# M2_NVME.net
KiCad netlist of a schematic drawn in Altium Designer
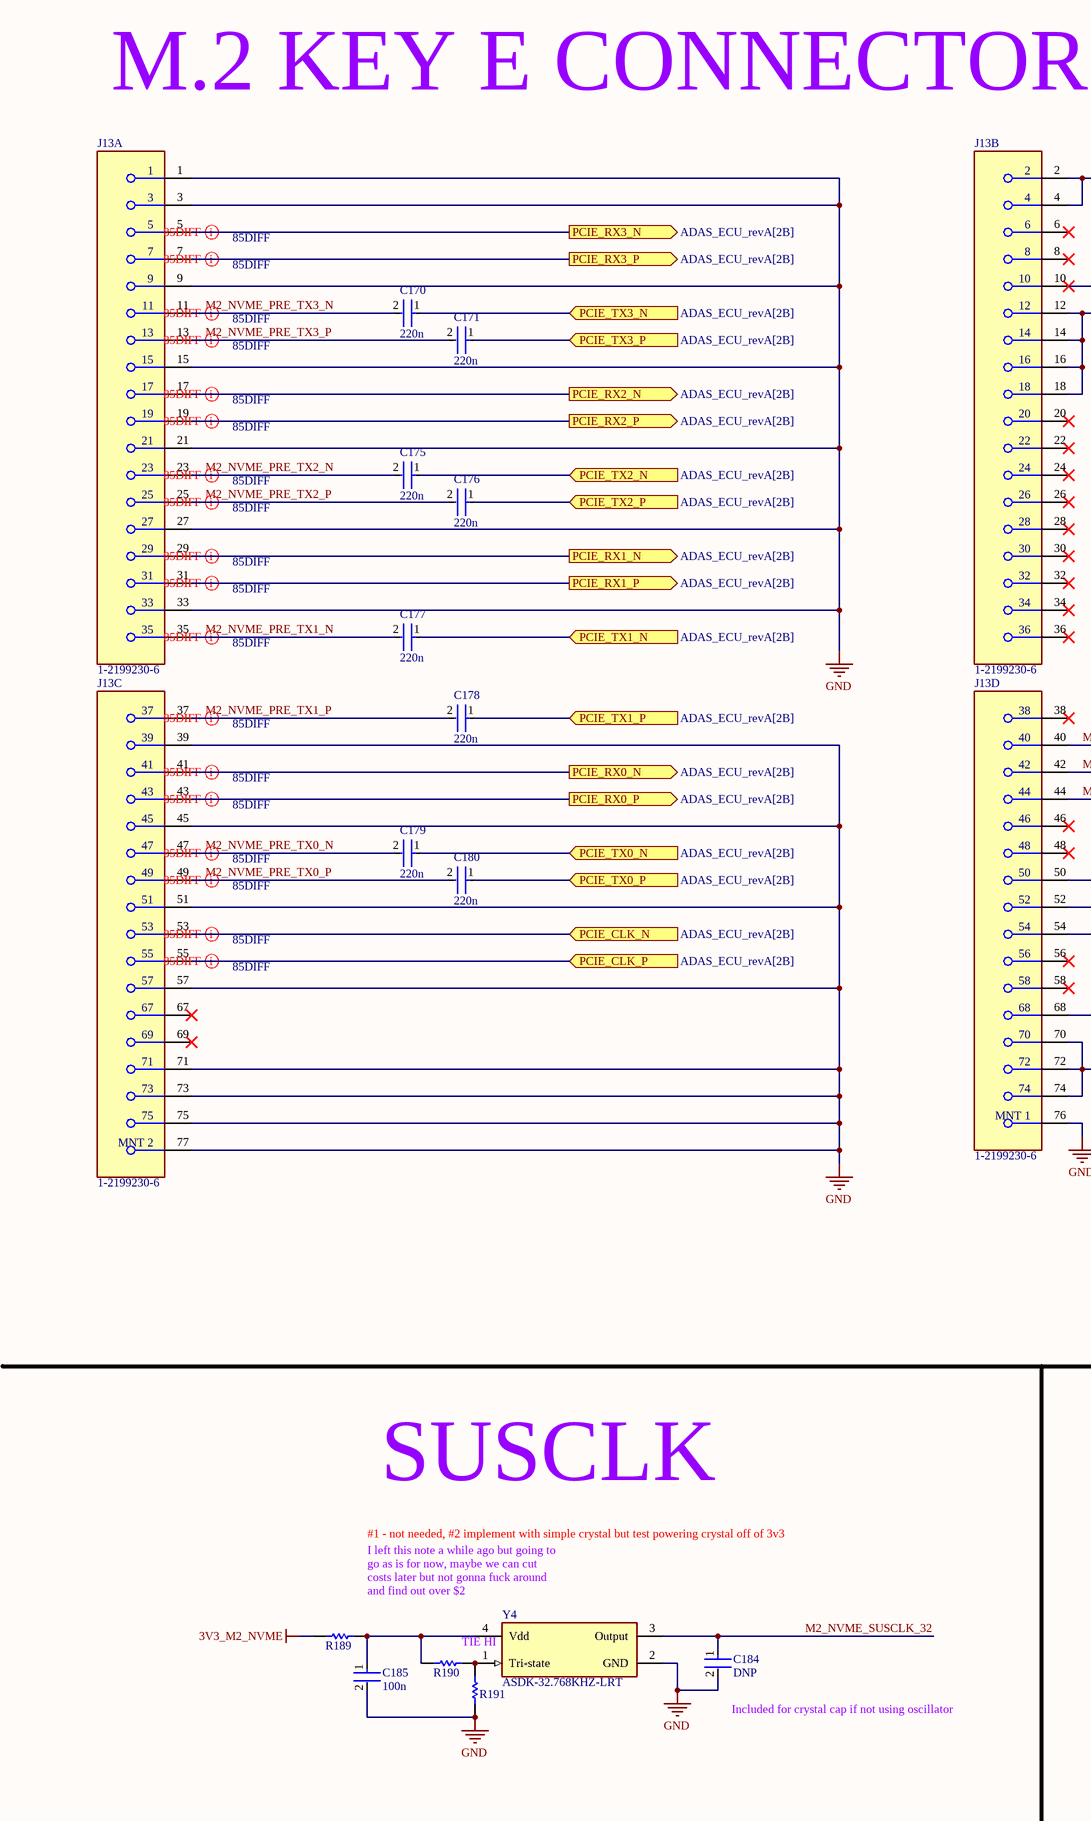
[diagram p0: M2_NVME.SchDoc, left]
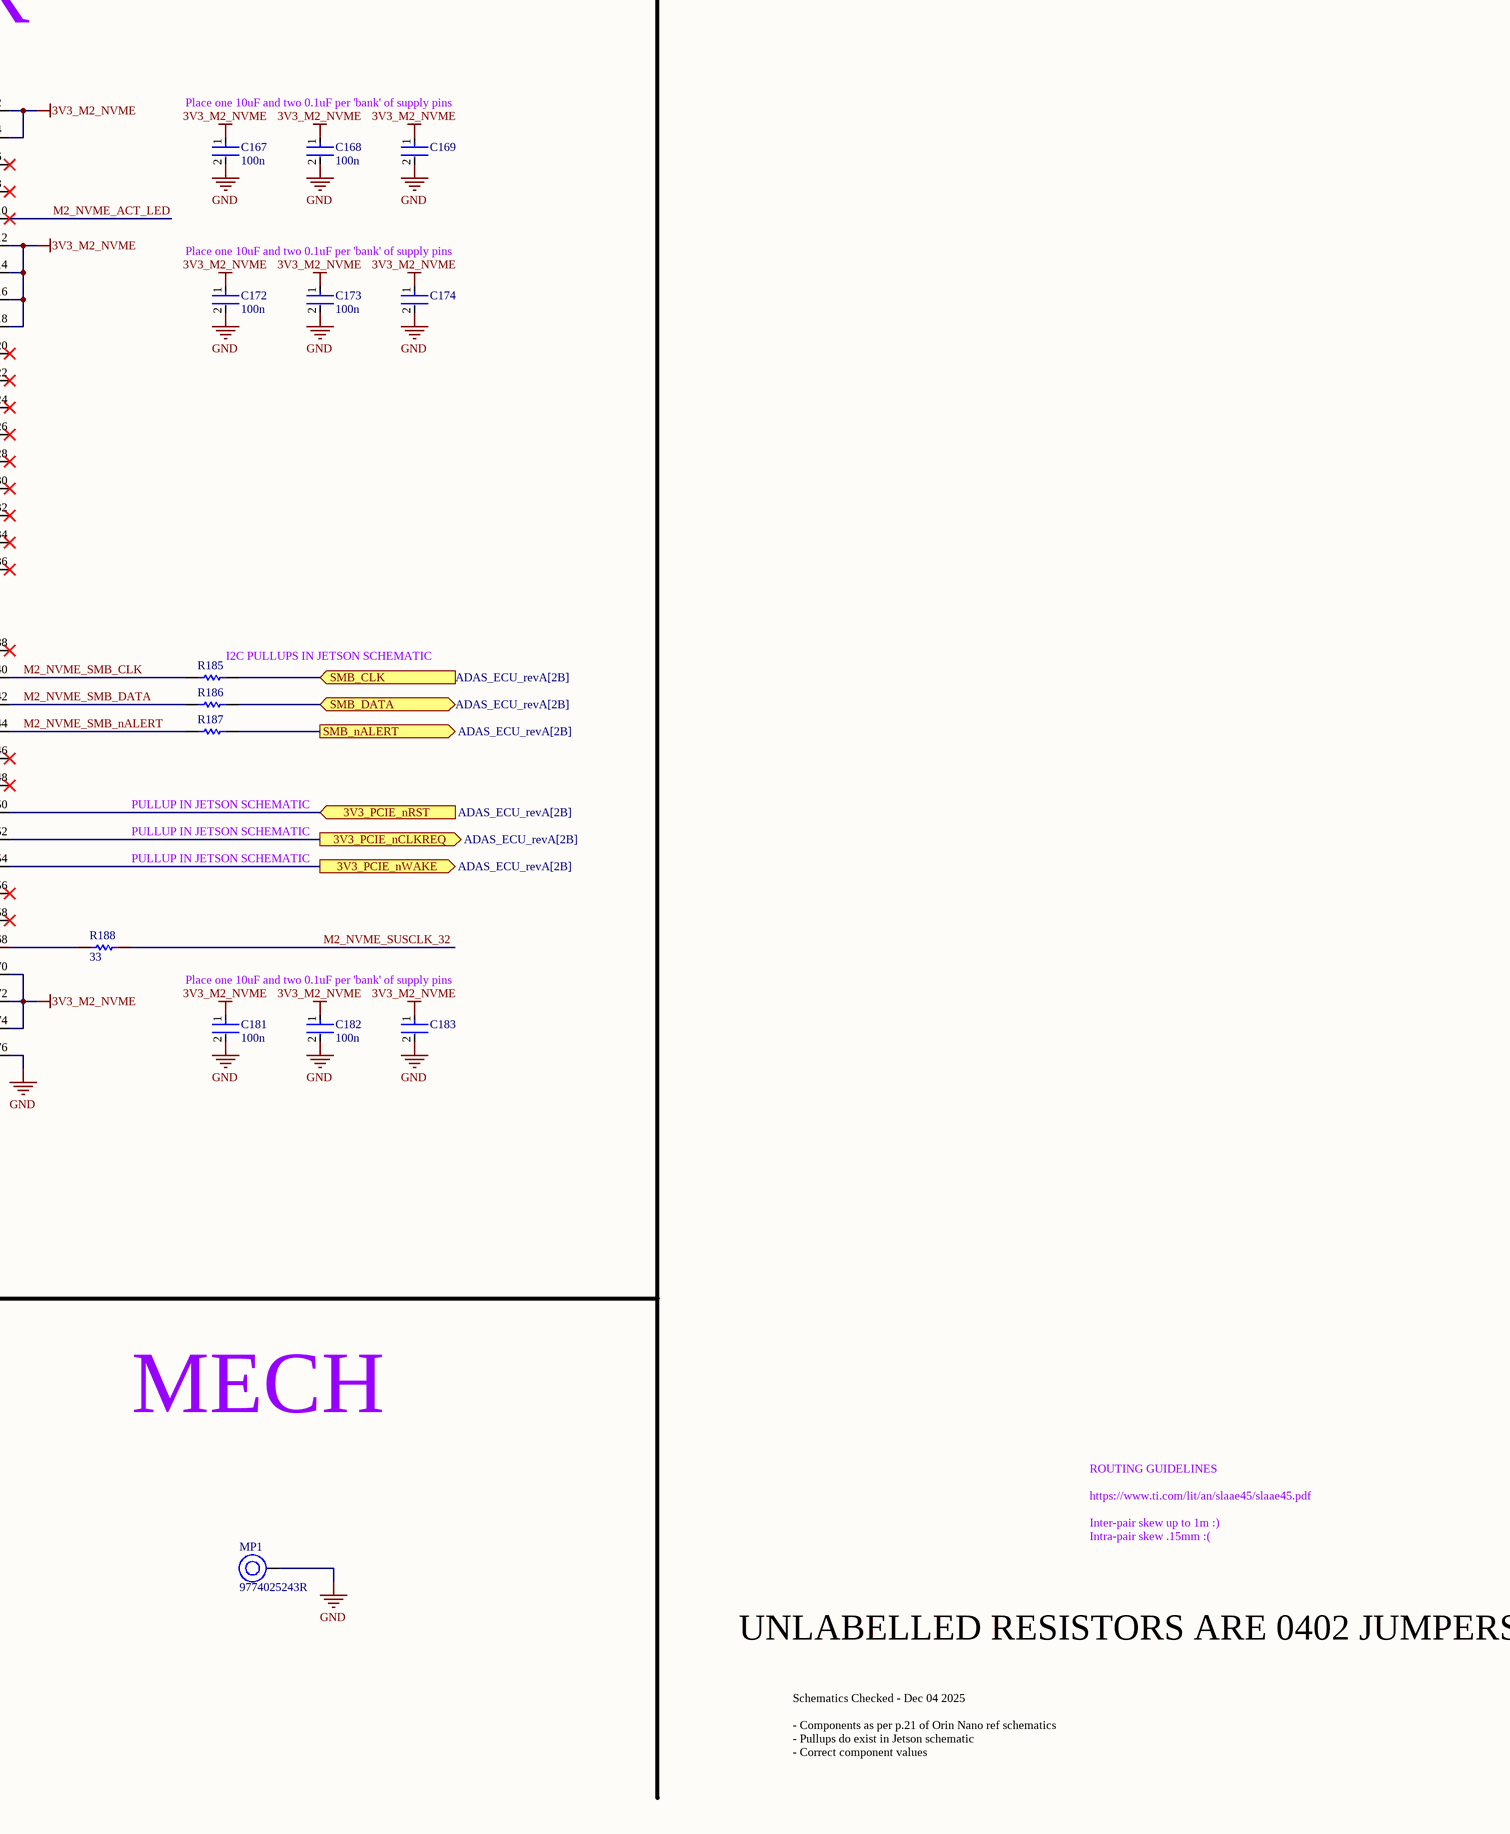
[diagram p1: M2_NVME.SchDoc, right]

(export (version "E")
  (design (tool "Eeschema 10.0.6"))
  (components
    (comp (ref "C167")
      (value "100n")
      (footprint "FP-0402-L_1_0_0_05-W_0_5-IPC_A")
      (description "LARGE PADS, 0402 CAP, CHANGE COMMENT TO MATCH REAL P/N")
      (libsource (lib "Space Concordia") (part "b4654b650e69147ec39a6b967a45e02"))
    )
    (comp (ref "C168")
      (value "100n")
      (footprint "FP-0402-L_1_0_0_05-W_0_5-IPC_A")
      (description "LARGE PADS, 0402 CAP, CHANGE COMMENT TO MATCH REAL P/N")
      (libsource (lib "Space Concordia") (part "b4654b650e69147ec39a6b967a45e02"))
    )
    (comp (ref "C169")
      (value "GRM188R60J106ME47D")
      (footprint "FP-GRM188-0_1-e0_2_0_55-IPC_A")
      (description "Chip Multilayer Ceramic Capacitors for General Purpose, 0603, 10uF, X5R, 15%, 20%, 6.3V")
      (fields (field (name "VOLTAGE") "6.3V") (field (name "TOLERANCE") "20%"))
      (libsource (lib "Altium Content Vault") (part "02cd4be3c70576c341d710602a673aa"))
    )
    (comp (ref "C170")
      (value "220n")
      (footprint "FP-0402-L_1_0_0_05-W_0_5-IPC_A")
      (description "LARGE PADS, 0402 CAP, CHANGE COMMENT TO MATCH REAL P/N")
      (libsource (lib "Space Concordia") (part "b4654b650e69147ec39a6b967a45e02"))
    )
    (comp (ref "C171")
      (value "220n")
      (footprint "FP-0402-L_1_0_0_05-W_0_5-IPC_A")
      (description "LARGE PADS, 0402 CAP, CHANGE COMMENT TO MATCH REAL P/N")
      (libsource (lib "Space Concordia") (part "b4654b650e69147ec39a6b967a45e02"))
    )
    (comp (ref "C172")
      (value "100n")
      (footprint "FP-0402-L_1_0_0_05-W_0_5-IPC_A")
      (description "LARGE PADS, 0402 CAP, CHANGE COMMENT TO MATCH REAL P/N")
      (libsource (lib "Space Concordia") (part "b4654b650e69147ec39a6b967a45e02"))
    )
    (comp (ref "C173")
      (value "100n")
      (footprint "FP-0402-L_1_0_0_05-W_0_5-IPC_A")
      (description "LARGE PADS, 0402 CAP, CHANGE COMMENT TO MATCH REAL P/N")
      (libsource (lib "Space Concordia") (part "b4654b650e69147ec39a6b967a45e02"))
    )
    (comp (ref "C174")
      (value "GRM188R60J106ME47D")
      (footprint "FP-GRM188-0_1-e0_2_0_55-IPC_A")
      (description "Chip Multilayer Ceramic Capacitors for General Purpose, 0603, 10uF, X5R, 15%, 20%, 6.3V")
      (fields (field (name "VOLTAGE") "6.3V") (field (name "TOLERANCE") "20%"))
      (libsource (lib "Altium Content Vault") (part "02cd4be3c70576c341d710602a673aa"))
    )
    (comp (ref "C175")
      (value "220n")
      (footprint "FP-0402-L_1_0_0_05-W_0_5-IPC_A")
      (description "LARGE PADS, 0402 CAP, CHANGE COMMENT TO MATCH REAL P/N")
      (libsource (lib "Space Concordia") (part "b4654b650e69147ec39a6b967a45e02"))
    )
    (comp (ref "C176")
      (value "220n")
      (footprint "FP-0402-L_1_0_0_05-W_0_5-IPC_A")
      (description "LARGE PADS, 0402 CAP, CHANGE COMMENT TO MATCH REAL P/N")
      (libsource (lib "Space Concordia") (part "b4654b650e69147ec39a6b967a45e02"))
    )
    (comp (ref "C177")
      (value "220n")
      (footprint "FP-0402-L_1_0_0_05-W_0_5-IPC_A")
      (description "LARGE PADS, 0402 CAP, CHANGE COMMENT TO MATCH REAL P/N")
      (libsource (lib "Space Concordia") (part "b4654b650e69147ec39a6b967a45e02"))
    )
    (comp (ref "C178")
      (value "220n")
      (footprint "FP-0402-L_1_0_0_05-W_0_5-IPC_A")
      (description "LARGE PADS, 0402 CAP, CHANGE COMMENT TO MATCH REAL P/N")
      (libsource (lib "Space Concordia") (part "b4654b650e69147ec39a6b967a45e02"))
    )
    (comp (ref "C179")
      (value "220n")
      (footprint "FP-0402-L_1_0_0_05-W_0_5-IPC_A")
      (description "LARGE PADS, 0402 CAP, CHANGE COMMENT TO MATCH REAL P/N")
      (libsource (lib "Space Concordia") (part "b4654b650e69147ec39a6b967a45e02"))
    )
    (comp (ref "C180")
      (value "220n")
      (footprint "FP-0402-L_1_0_0_05-W_0_5-IPC_A")
      (description "LARGE PADS, 0402 CAP, CHANGE COMMENT TO MATCH REAL P/N")
      (libsource (lib "Space Concordia") (part "b4654b650e69147ec39a6b967a45e02"))
    )
    (comp (ref "C181")
      (value "100n")
      (footprint "FP-0402-L_1_0_0_05-W_0_5-IPC_A")
      (description "LARGE PADS, 0402 CAP, CHANGE COMMENT TO MATCH REAL P/N")
      (libsource (lib "Space Concordia") (part "b4654b650e69147ec39a6b967a45e02"))
    )
    (comp (ref "C182")
      (value "100n")
      (footprint "FP-0402-L_1_0_0_05-W_0_5-IPC_A")
      (description "LARGE PADS, 0402 CAP, CHANGE COMMENT TO MATCH REAL P/N")
      (libsource (lib "Space Concordia") (part "b4654b650e69147ec39a6b967a45e02"))
    )
    (comp (ref "C183")
      (value "GRM188R60J106ME47D")
      (footprint "FP-GRM188-0_1-e0_2_0_55-IPC_A")
      (description "Chip Multilayer Ceramic Capacitors for General Purpose, 0603, 10uF, X5R, 15%, 20%, 6.3V")
      (fields (field (name "VOLTAGE") "6.3V") (field (name "TOLERANCE") "20%"))
      (libsource (lib "Altium Content Vault") (part "02cd4be3c70576c341d710602a673aa"))
    )
    (comp (ref "C184")
      (value "DNP")
      (footprint "FP-0402-L_1_0_0_05-W_0_5-IPC_A")
      (description "LARGE PADS, 0402 CAP, CHANGE COMMENT TO MATCH REAL P/N")
      (libsource (lib "Space Concordia") (part "b4654b650e69147ec39a6b967a45e02"))
    )
    (comp (ref "C185")
      (value "100n")
      (footprint "FP-0402-L_1_0_0_05-W_0_5-IPC_A")
      (description "LARGE PADS, 0402 CAP, CHANGE COMMENT TO MATCH REAL P/N")
      (libsource (lib "Space Concordia") (part "b4654b650e69147ec39a6b967a45e02"))
    )
    (comp (ref "J13")
      (value "1-2199230-6")
      (footprint "FP-1-2199230-6-MFG")
      (description "CONN EDGE DUAL FMALE 67POS 0.020")
      (fields
        (field (name "MANUFACTURER") "TE")
        (field (name "OCTOPART") "https://octopart.com/1-2199230-6-te+connectivity-34969376")
      )
      (libsource (lib "Altium Content Vault") (part "bdc5cd39fb5e3adfc3cf7d042564072"))
    )
    (comp (ref "MP1")
      (value "9774025243R")
      (footprint "9774025243")
      (description "9774025243R Spacer Material: Steel, Tin-Plated Mounting: SMT Series: WA-SMST Thread D: M2")
      (libsource (lib "Altium Content Vault") (part "Spacer"))
    )
    (comp (ref "R185")
      (value "DNP")
      (footprint "RESC1005X40X25ML05T05")
      (description "READ THE NAME")
      (libsource (lib "Space Concordia") (part "CMP-009-00206-2"))
    )
    (comp (ref "R186")
      (value "DNP")
      (footprint "RESC1005X40X25ML05T05")
      (description "READ THE NAME")
      (libsource (lib "Space Concordia") (part "CMP-009-00206-2"))
    )
    (comp (ref "R187")
      (value "DNP")
      (footprint "RESC1005X40X25ML05T05")
      (description "READ THE NAME")
      (libsource (lib "Space Concordia") (part "CMP-009-00206-2"))
    )
    (comp (ref "R188")
      (value "33")
      (footprint "R0603B")
      (description "Resistor")
      (libsource (lib "Space Concordia") (part "Resistor"))
    )
    (comp (ref "R189")
      (value "0402 JUMPER")
      (footprint "RESC1005X40X25ML05T05")
      (description "READ THE NAME")
      (libsource (lib "Space Concordia") (part "CMP-009-00206-2"))
    )
    (comp (ref "R190")
      (value "0402 JUMPER")
      (footprint "RESC1005X40X25ML05T05")
      (description "READ THE NAME")
      (libsource (lib "Space Concordia") (part "CMP-009-00206-2"))
    )
    (comp (ref "R191")
      (value "DNP")
      (footprint "RESC1005X40X25ML05T05")
      (description "READ THE NAME")
      (libsource (lib "Space Concordia") (part "CMP-009-00206-2"))
    )
    (comp (ref "Y4")
      (value "ASDK-32.768KHZ-LRT")
      (footprint "FP-ASDK-MFG")
      (description "XTAL OSC XO 32.7680KHZ CMOS SMD")
      (libsource (lib "Altium Content Vault") (part "a7425352bb6ebc83bfd0f12a23808e7"))
    )
  )
  (nets
    (net (code "1") (name "/3V3_PCIE_nCLKREQ") (class "Default")
      (node (ref "J13") (pin "52") (pinfunction "52_52") (pintype "passive"))
    )
    (net (code "2") (name "/3V3_PCIE_nRST") (class "Default")
      (node (ref "J13") (pin "50") (pinfunction "50_50") (pintype "passive"))
    )
    (net (code "3") (name "/3V3_PCIE_nWAKE") (class "Default")
      (node (ref "J13") (pin "54") (pinfunction "54_54") (pintype "passive"))
    )
    (net (code "4") (name "/M2_NVME_ACT_LED") (class "Default")
      (node (ref "J13") (pin "10") (pinfunction "10_10") (pintype "passive+no_connect"))
    )
    (net (code "5") (name "/M2_NVME_PRE_TX0_N") (class "Default")
      (node (ref "C179") (pin "2") (pinfunction "2_2") (pintype "passive"))
      (node (ref "J13") (pin "47") (pinfunction "47_47") (pintype "passive"))
    )
    (net (code "6") (name "/M2_NVME_PRE_TX0_P") (class "Default")
      (node (ref "C180") (pin "2") (pinfunction "2_2") (pintype "passive"))
      (node (ref "J13") (pin "49") (pinfunction "49_49") (pintype "passive"))
    )
    (net (code "7") (name "/M2_NVME_PRE_TX1_N") (class "Default")
      (node (ref "C177") (pin "2") (pinfunction "2_2") (pintype "passive"))
      (node (ref "J13") (pin "35") (pinfunction "35_35") (pintype "passive"))
    )
    (net (code "8") (name "/M2_NVME_PRE_TX1_P") (class "Default")
      (node (ref "C178") (pin "2") (pinfunction "2_2") (pintype "passive"))
      (node (ref "J13") (pin "37") (pinfunction "37_37") (pintype "passive"))
    )
    (net (code "9") (name "/M2_NVME_PRE_TX2_N") (class "Default")
      (node (ref "C175") (pin "2") (pinfunction "2_2") (pintype "passive"))
      (node (ref "J13") (pin "23") (pinfunction "23_23") (pintype "passive"))
    )
    (net (code "10") (name "/M2_NVME_PRE_TX2_P") (class "Default")
      (node (ref "C176") (pin "2") (pinfunction "2_2") (pintype "passive"))
      (node (ref "J13") (pin "25") (pinfunction "25_25") (pintype "passive"))
    )
    (net (code "11") (name "/M2_NVME_PRE_TX3_N") (class "Default")
      (node (ref "C170") (pin "2") (pinfunction "2_2") (pintype "passive"))
      (node (ref "J13") (pin "11") (pinfunction "11_11") (pintype "passive"))
    )
    (net (code "12") (name "/M2_NVME_PRE_TX3_P") (class "Default")
      (node (ref "C171") (pin "2") (pinfunction "2_2") (pintype "passive"))
      (node (ref "J13") (pin "13") (pinfunction "13_13") (pintype "passive"))
    )
    (net (code "13") (name "/M2_NVME_SMB_CLK") (class "Default")
      (node (ref "J13") (pin "40") (pinfunction "40_40") (pintype "passive"))
      (node (ref "R185") (pin "1") (pinfunction "1_1") (pintype "passive"))
    )
    (net (code "14") (name "/M2_NVME_SMB_DATA") (class "Default")
      (node (ref "J13") (pin "42") (pinfunction "42_42") (pintype "passive"))
      (node (ref "R186") (pin "1") (pinfunction "1_1") (pintype "passive"))
    )
    (net (code "15") (name "/M2_NVME_SMB_nALERT") (class "Default")
      (node (ref "J13") (pin "44") (pinfunction "44_44") (pintype "passive"))
      (node (ref "R187") (pin "1") (pinfunction "1_1") (pintype "passive"))
    )
    (net (code "16") (name "/M2_NVME_SUSCLK_32") (class "Default")
      (node (ref "C184") (pin "1") (pinfunction "1_1") (pintype "passive"))
      (node (ref "R188") (pin "1") (pinfunction "1_1") (pintype "passive"))
      (node (ref "Y4") (pin "3") (pinfunction "Output_3") (pintype "tri_state"))
    )
    (net (code "17") (name "/PCIE_CLK_N") (class "Default")
      (node (ref "J13") (pin "53") (pinfunction "53_53") (pintype "passive"))
    )
    (net (code "18") (name "/PCIE_CLK_P") (class "Default")
      (node (ref "J13") (pin "55") (pinfunction "55_55") (pintype "passive"))
    )
    (net (code "19") (name "/PCIE_RX0_N") (class "Default")
      (node (ref "J13") (pin "41") (pinfunction "41_41") (pintype "passive"))
    )
    (net (code "20") (name "/PCIE_RX0_P") (class "Default")
      (node (ref "J13") (pin "43") (pinfunction "43_43") (pintype "passive"))
    )
    (net (code "21") (name "/PCIE_RX1_N") (class "Default")
      (node (ref "J13") (pin "29") (pinfunction "29_29") (pintype "passive"))
    )
    (net (code "22") (name "/PCIE_RX1_P") (class "Default")
      (node (ref "J13") (pin "31") (pinfunction "31_31") (pintype "passive"))
    )
    (net (code "23") (name "/PCIE_RX2_N") (class "Default")
      (node (ref "J13") (pin "17") (pinfunction "17_17") (pintype "passive"))
    )
    (net (code "24") (name "/PCIE_RX2_P") (class "Default")
      (node (ref "J13") (pin "19") (pinfunction "19_19") (pintype "passive"))
    )
    (net (code "25") (name "/PCIE_RX3_N") (class "Default")
      (node (ref "J13") (pin "5") (pinfunction "5_5") (pintype "passive"))
    )
    (net (code "26") (name "/PCIE_RX3_P") (class "Default")
      (node (ref "J13") (pin "7") (pinfunction "7_7") (pintype "passive"))
    )
    (net (code "27") (name "/PCIE_TX0_N") (class "Default")
      (node (ref "C179") (pin "1") (pinfunction "1_1") (pintype "passive"))
    )
    (net (code "28") (name "/PCIE_TX0_P") (class "Default")
      (node (ref "C180") (pin "1") (pinfunction "1_1") (pintype "passive"))
    )
    (net (code "29") (name "/PCIE_TX1_N") (class "Default")
      (node (ref "C177") (pin "1") (pinfunction "1_1") (pintype "passive"))
    )
    (net (code "30") (name "/PCIE_TX1_P") (class "Default")
      (node (ref "C178") (pin "1") (pinfunction "1_1") (pintype "passive"))
    )
    (net (code "31") (name "/PCIE_TX2_N") (class "Default")
      (node (ref "C175") (pin "1") (pinfunction "1_1") (pintype "passive"))
    )
    (net (code "32") (name "/PCIE_TX2_P") (class "Default")
      (node (ref "C176") (pin "1") (pinfunction "1_1") (pintype "passive"))
    )
    (net (code "33") (name "/PCIE_TX3_N") (class "Default")
      (node (ref "C170") (pin "1") (pinfunction "1_1") (pintype "passive"))
    )
    (net (code "34") (name "/PCIE_TX3_P") (class "Default")
      (node (ref "C171") (pin "1") (pinfunction "1_1") (pintype "passive"))
    )
    (net (code "35") (name "/SMB_CLK") (class "Default")
      (node (ref "R185") (pin "2") (pinfunction "2_2") (pintype "passive"))
    )
    (net (code "36") (name "/SMB_DATA") (class "Default")
      (node (ref "R186") (pin "2") (pinfunction "2_2") (pintype "passive"))
    )
    (net (code "37") (name "/SMB_nALERT") (class "Default")
      (node (ref "R187") (pin "2") (pinfunction "2_2") (pintype "passive"))
    )
    (net (code "38") (name "3V3_M2_NVME") (class "Default")
      (node (ref "C167") (pin "1") (pinfunction "1_1") (pintype "passive"))
      (node (ref "C168") (pin "1") (pinfunction "1_1") (pintype "passive"))
      (node (ref "C169") (pin "1") (pinfunction "1_1") (pintype "passive"))
      (node (ref "C172") (pin "1") (pinfunction "1_1") (pintype "passive"))
      (node (ref "C173") (pin "1") (pinfunction "1_1") (pintype "passive"))
      (node (ref "C174") (pin "1") (pinfunction "1_1") (pintype "passive"))
      (node (ref "C181") (pin "1") (pinfunction "1_1") (pintype "passive"))
      (node (ref "C182") (pin "1") (pinfunction "1_1") (pintype "passive"))
      (node (ref "C183") (pin "1") (pinfunction "1_1") (pintype "passive"))
      (node (ref "J13") (pin "12") (pinfunction "12_12") (pintype "passive"))
      (node (ref "J13") (pin "14") (pinfunction "14_14") (pintype "passive"))
      (node (ref "J13") (pin "16") (pinfunction "16_16") (pintype "passive"))
      (node (ref "J13") (pin "18") (pinfunction "18_18") (pintype "passive"))
      (node (ref "J13") (pin "2") (pinfunction "2_2") (pintype "passive"))
      (node (ref "J13") (pin "4") (pinfunction "4_4") (pintype "passive"))
      (node (ref "J13") (pin "70") (pinfunction "70_70") (pintype "passive"))
      (node (ref "J13") (pin "72") (pinfunction "72_72") (pintype "passive"))
      (node (ref "J13") (pin "74") (pinfunction "74_74") (pintype "passive"))
      (node (ref "R189") (pin "1") (pinfunction "1_1") (pintype "passive"))
    )
    (net (code "39") (name "GND") (class "Default")
      (node (ref "C167") (pin "2") (pinfunction "2_2") (pintype "passive"))
      (node (ref "C168") (pin "2") (pinfunction "2_2") (pintype "passive"))
      (node (ref "C169") (pin "2") (pinfunction "2_2") (pintype "passive"))
      (node (ref "C172") (pin "2") (pinfunction "2_2") (pintype "passive"))
      (node (ref "C173") (pin "2") (pinfunction "2_2") (pintype "passive"))
      (node (ref "C174") (pin "2") (pinfunction "2_2") (pintype "passive"))
      (node (ref "C181") (pin "2") (pinfunction "2_2") (pintype "passive"))
      (node (ref "C182") (pin "2") (pinfunction "2_2") (pintype "passive"))
      (node (ref "C183") (pin "2") (pinfunction "2_2") (pintype "passive"))
      (node (ref "C184") (pin "2") (pinfunction "2_2") (pintype "passive"))
      (node (ref "C185") (pin "2") (pinfunction "2_2") (pintype "passive"))
      (node (ref "J13") (pin "1") (pinfunction "1_1") (pintype "passive"))
      (node (ref "J13") (pin "15") (pinfunction "15_15") (pintype "passive"))
      (node (ref "J13") (pin "21") (pinfunction "21_21") (pintype "passive"))
      (node (ref "J13") (pin "27") (pinfunction "27_27") (pintype "passive"))
      (node (ref "J13") (pin "3") (pinfunction "3_3") (pintype "passive"))
      (node (ref "J13") (pin "33") (pinfunction "33_33") (pintype "passive"))
      (node (ref "J13") (pin "39") (pinfunction "39_39") (pintype "passive"))
      (node (ref "J13") (pin "45") (pinfunction "45_45") (pintype "passive"))
      (node (ref "J13") (pin "51") (pinfunction "51_51") (pintype "passive"))
      (node (ref "J13") (pin "57") (pinfunction "57_57") (pintype "passive"))
      (node (ref "J13") (pin "71") (pinfunction "71_71") (pintype "passive"))
      (node (ref "J13") (pin "73") (pinfunction "73_73") (pintype "passive"))
      (node (ref "J13") (pin "75") (pinfunction "75_75") (pintype "passive"))
      (node (ref "J13") (pin "76") (pinfunction "MNT_1_76") (pintype "passive"))
      (node (ref "J13") (pin "77") (pinfunction "MNT_2_77") (pintype "passive"))
      (node (ref "J13") (pin "9") (pinfunction "9_9") (pintype "passive"))
      (node (ref "MP1") (pin "1") (pinfunction "1_1") (pintype "passive"))
      (node (ref "R191") (pin "1") (pinfunction "1_1") (pintype "passive"))
      (node (ref "Y4") (pin "2") (pinfunction "GND_2") (pintype "power_in"))
    )
    (net (code "40") (name "Net-(J13-Pad68)") (class "Default")
      (node (ref "J13") (pin "68") (pinfunction "68_68") (pintype "passive"))
      (node (ref "R188") (pin "2") (pinfunction "2_2") (pintype "passive"))
    )
    (net (code "41") (name "Net-(Y4-Tri-state)") (class "Default")
      (node (ref "R190") (pin "2") (pinfunction "2_2") (pintype "passive"))
      (node (ref "R191") (pin "2") (pinfunction "2_2") (pintype "passive"))
      (node (ref "Y4") (pin "1") (pinfunction "Tri-state_1") (pintype "input"))
    )
    (net (code "42") (name "Net-(Y4-Vdd)") (class "Default")
      (node (ref "C185") (pin "1") (pinfunction "1_1") (pintype "passive"))
      (node (ref "R189") (pin "2") (pinfunction "2_2") (pintype "passive"))
      (node (ref "R190") (pin "1") (pinfunction "1_1") (pintype "passive"))
      (node (ref "Y4") (pin "4") (pinfunction "Vdd_4") (pintype "power_in"))
    )
    (net (code "43") (name "unconnected-(J13-Pad6)") (class "Default")
      (node (ref "J13") (pin "6") (pinfunction "6_6") (pintype "passive+no_connect"))
    )
    (net (code "44") (name "unconnected-(J13-Pad8)") (class "Default")
      (node (ref "J13") (pin "8") (pinfunction "8_8") (pintype "passive+no_connect"))
    )
    (net (code "45") (name "unconnected-(J13-Pad20)") (class "Default")
      (node (ref "J13") (pin "20") (pinfunction "20_20") (pintype "passive+no_connect"))
    )
    (net (code "46") (name "unconnected-(J13-Pad22)") (class "Default")
      (node (ref "J13") (pin "22") (pinfunction "22_22") (pintype "passive+no_connect"))
    )
    (net (code "47") (name "unconnected-(J13-Pad24)") (class "Default")
      (node (ref "J13") (pin "24") (pinfunction "24_24") (pintype "passive+no_connect"))
    )
    (net (code "48") (name "unconnected-(J13-Pad26)") (class "Default")
      (node (ref "J13") (pin "26") (pinfunction "26_26") (pintype "passive+no_connect"))
    )
    (net (code "49") (name "unconnected-(J13-Pad28)") (class "Default")
      (node (ref "J13") (pin "28") (pinfunction "28_28") (pintype "passive+no_connect"))
    )
    (net (code "50") (name "unconnected-(J13-Pad30)") (class "Default")
      (node (ref "J13") (pin "30") (pinfunction "30_30") (pintype "passive+no_connect"))
    )
    (net (code "51") (name "unconnected-(J13-Pad32)") (class "Default")
      (node (ref "J13") (pin "32") (pinfunction "32_32") (pintype "passive+no_connect"))
    )
    (net (code "52") (name "unconnected-(J13-Pad34)") (class "Default")
      (node (ref "J13") (pin "34") (pinfunction "34_34") (pintype "passive+no_connect"))
    )
    (net (code "53") (name "unconnected-(J13-Pad36)") (class "Default")
      (node (ref "J13") (pin "36") (pinfunction "36_36") (pintype "passive+no_connect"))
    )
    (net (code "54") (name "unconnected-(J13-Pad38)") (class "Default")
      (node (ref "J13") (pin "38") (pinfunction "38_38") (pintype "passive+no_connect"))
    )
    (net (code "55") (name "unconnected-(J13-Pad46)") (class "Default")
      (node (ref "J13") (pin "46") (pinfunction "46_46") (pintype "passive+no_connect"))
    )
    (net (code "56") (name "unconnected-(J13-Pad48)") (class "Default")
      (node (ref "J13") (pin "48") (pinfunction "48_48") (pintype "passive+no_connect"))
    )
    (net (code "57") (name "unconnected-(J13-Pad56)") (class "Default")
      (node (ref "J13") (pin "56") (pinfunction "56_56") (pintype "passive+no_connect"))
    )
    (net (code "58") (name "unconnected-(J13-Pad58)") (class "Default")
      (node (ref "J13") (pin "58") (pinfunction "58_58") (pintype "passive+no_connect"))
    )
    (net (code "59") (name "unconnected-(J13-Pad67)") (class "Default")
      (node (ref "J13") (pin "67") (pinfunction "67_67") (pintype "passive+no_connect"))
    )
    (net (code "60") (name "unconnected-(J13-Pad69)") (class "Default")
      (node (ref "J13") (pin "69") (pinfunction "69_69") (pintype "passive+no_connect"))
    )
  )
)
